# mega8_mega16.net
KiCad netlist of a schematic drawn in Altium Designer
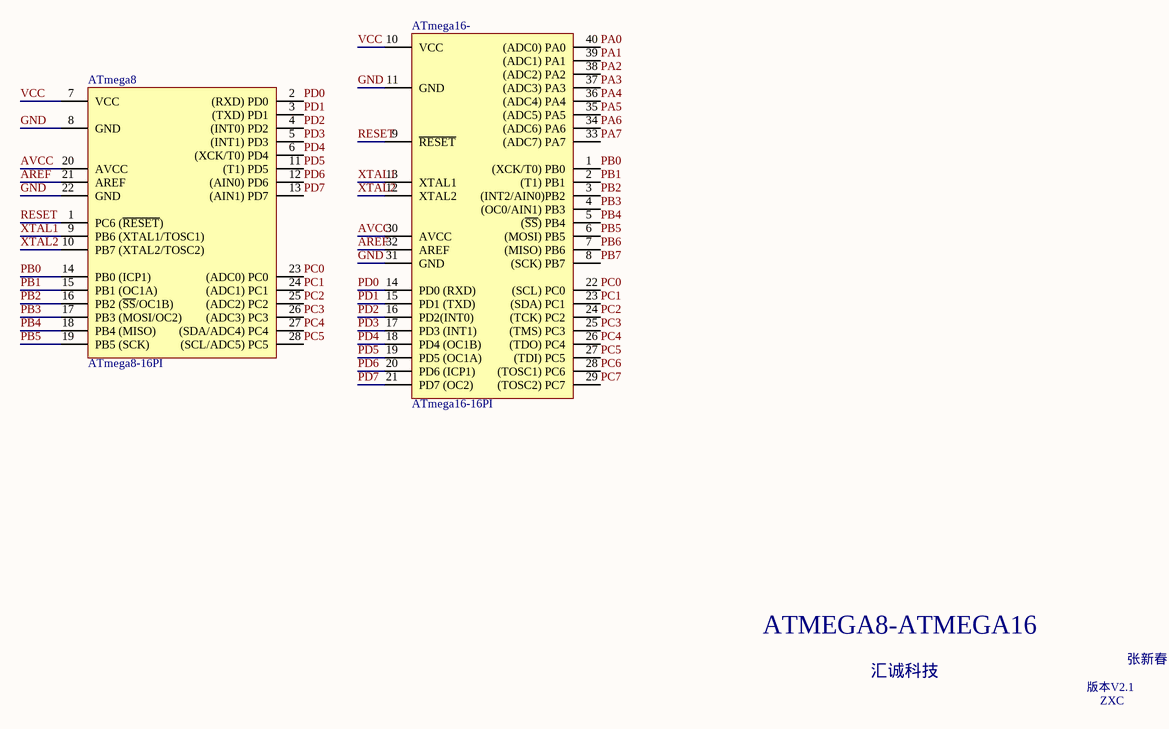
[diagram p0: mega8_mega16.SchDoc]

(export (version "E")
  (design (tool "Eeschema 10.0.6"))
  (components
    (comp (ref "ATmega8")
      (value "ATmega8-16PI")
      (footprint "底座DIP-28/引脚7.62mm")
      (description "8 位微处理器/28引脚")
      (fields (field (name "发布者") "磊元工作室"))
      (libsource (lib "微控制处理器") (part "ATmega8-P"))
    )
    (comp (ref "ATmega16-")
      (value "ATmega16-16PI")
      (footprint "底座DIP-40/引脚15.24mm")
      (description "8 位微处理器/40引脚")
      (fields (field (name "发布者") "磊元工作室"))
      (libsource (lib "微控制处理器") (part "ATmega16-P"))
    )
  )
  (nets
    (net (code "1") (name "/AREF") (class "Default")
      (node (ref "ATmega16-") (pin "32") (pinfunction "AREF_32") (pintype "passive"))
      (node (ref "ATmega8") (pin "21") (pinfunction "AREF_21") (pintype "passive"))
    )
    (net (code "2") (name "/AVCC") (class "Default")
      (node (ref "ATmega16-") (pin "30") (pinfunction "AVCC_30") (pintype "passive"))
      (node (ref "ATmega8") (pin "20") (pinfunction "AVCC_20") (pintype "passive"))
    )
    (net (code "3") (name "/GND") (class "Default")
      (node (ref "ATmega16-") (pin "11") (pinfunction "GND_11") (pintype "passive"))
      (node (ref "ATmega16-") (pin "31") (pinfunction "GND_31") (pintype "passive"))
      (node (ref "ATmega8") (pin "22") (pinfunction "GND_22") (pintype "passive"))
      (node (ref "ATmega8") (pin "8") (pinfunction "GND_8") (pintype "passive"))
    )
    (net (code "4") (name "/PA0") (class "Default")
      (node (ref "ATmega16-") (pin "40") (pinfunction "(ADC0)_PA0_40") (pintype "passive"))
    )
    (net (code "5") (name "/PA1") (class "Default")
      (node (ref "ATmega16-") (pin "39") (pinfunction "(ADC1)_PA1_39") (pintype "passive"))
    )
    (net (code "6") (name "/PA2") (class "Default")
      (node (ref "ATmega16-") (pin "38") (pinfunction "(ADC2)_PA2_38") (pintype "passive"))
    )
    (net (code "7") (name "/PA3") (class "Default")
      (node (ref "ATmega16-") (pin "37") (pinfunction "(ADC3)_PA3_37") (pintype "passive"))
    )
    (net (code "8") (name "/PA4") (class "Default")
      (node (ref "ATmega16-") (pin "36") (pinfunction "(ADC4)_PA4_36") (pintype "passive"))
    )
    (net (code "9") (name "/PA5") (class "Default")
      (node (ref "ATmega16-") (pin "35") (pinfunction "(ADC5)_PA5_35") (pintype "passive"))
    )
    (net (code "10") (name "/PA6") (class "Default")
      (node (ref "ATmega16-") (pin "34") (pinfunction "(ADC6)_PA6_34") (pintype "passive"))
    )
    (net (code "11") (name "/PA7") (class "Default")
      (node (ref "ATmega16-") (pin "33") (pinfunction "(ADC7)_PA7_33") (pintype "passive"))
    )
    (net (code "12") (name "/PB0") (class "Default")
      (node (ref "ATmega16-") (pin "1") (pinfunction "(XCK/T0)_PB0_1") (pintype "passive"))
      (node (ref "ATmega8") (pin "14") (pinfunction "PB0_(ICP1)_14") (pintype "passive"))
    )
    (net (code "13") (name "/PB1") (class "Default")
      (node (ref "ATmega16-") (pin "2") (pinfunction "(T1)_PB1_2") (pintype "passive"))
      (node (ref "ATmega8") (pin "15") (pinfunction "PB1_(OC1A)_15") (pintype "passive"))
    )
    (net (code "14") (name "/PB2") (class "Default")
      (node (ref "ATmega16-") (pin "3") (pinfunction "(INT2/AIN0)PB2_3") (pintype "passive"))
      (node (ref "ATmega8") (pin "16") (pinfunction "PB2_(~{SS}/OC1B)_16") (pintype "passive"))
    )
    (net (code "15") (name "/PB3") (class "Default")
      (node (ref "ATmega16-") (pin "4") (pinfunction "(OC0/AIN1)_PB3_4") (pintype "passive"))
      (node (ref "ATmega8") (pin "17") (pinfunction "PB3_(MOSI/OC2)_17") (pintype "passive"))
    )
    (net (code "16") (name "/PB4") (class "Default")
      (node (ref "ATmega16-") (pin "5") (pinfunction "(~{SS})_PB4_5") (pintype "passive"))
      (node (ref "ATmega8") (pin "18") (pinfunction "PB4_(MISO)_18") (pintype "passive"))
    )
    (net (code "17") (name "/PB5") (class "Default")
      (node (ref "ATmega16-") (pin "6") (pinfunction "(MOSI)_PB5_6") (pintype "passive"))
      (node (ref "ATmega8") (pin "19") (pinfunction "PB5_(SCK)_19") (pintype "passive"))
    )
    (net (code "18") (name "/PB6") (class "Default")
      (node (ref "ATmega16-") (pin "7") (pinfunction "(MISO)_PB6_7") (pintype "passive"))
    )
    (net (code "19") (name "/PB7") (class "Default")
      (node (ref "ATmega16-") (pin "8") (pinfunction "(SCK)_PB7_8") (pintype "passive"))
    )
    (net (code "20") (name "/PC0") (class "Default")
      (node (ref "ATmega16-") (pin "22") (pinfunction "(SCL)_PC0_22") (pintype "passive"))
      (node (ref "ATmega8") (pin "23") (pinfunction "(ADC0)_PC0_23") (pintype "passive"))
    )
    (net (code "21") (name "/PC1") (class "Default")
      (node (ref "ATmega16-") (pin "23") (pinfunction "(SDA)_PC1_23") (pintype "passive"))
      (node (ref "ATmega8") (pin "24") (pinfunction "(ADC1)_PC1_24") (pintype "passive"))
    )
    (net (code "22") (name "/PC2") (class "Default")
      (node (ref "ATmega16-") (pin "24") (pinfunction "(TCK)_PC2_24") (pintype "passive"))
      (node (ref "ATmega8") (pin "25") (pinfunction "(ADC2)_PC2_25") (pintype "passive"))
    )
    (net (code "23") (name "/PC3") (class "Default")
      (node (ref "ATmega16-") (pin "25") (pinfunction "(TMS)_PC3_25") (pintype "passive"))
      (node (ref "ATmega8") (pin "26") (pinfunction "(ADC3)_PC3_26") (pintype "passive"))
    )
    (net (code "24") (name "/PC4") (class "Default")
      (node (ref "ATmega16-") (pin "26") (pinfunction "(TDO)_PC4_26") (pintype "passive"))
      (node (ref "ATmega8") (pin "27") (pinfunction "(SDA/ADC4)_PC4_27") (pintype "passive"))
    )
    (net (code "25") (name "/PC5") (class "Default")
      (node (ref "ATmega16-") (pin "27") (pinfunction "(TDI)_PC5_27") (pintype "passive"))
      (node (ref "ATmega8") (pin "28") (pinfunction "(SCL/ADC5)_PC5_28") (pintype "passive"))
    )
    (net (code "26") (name "/PC6") (class "Default")
      (node (ref "ATmega16-") (pin "28") (pinfunction "(TOSC1)_PC6_28") (pintype "passive"))
    )
    (net (code "27") (name "/PC7") (class "Default")
      (node (ref "ATmega16-") (pin "29") (pinfunction "(TOSC2)_PC7_29") (pintype "passive"))
    )
    (net (code "28") (name "/PD0") (class "Default")
      (node (ref "ATmega16-") (pin "14") (pinfunction "PD0_(RXD)_14") (pintype "passive"))
      (node (ref "ATmega8") (pin "2") (pinfunction "(RXD)_PD0_2") (pintype "passive"))
    )
    (net (code "29") (name "/PD1") (class "Default")
      (node (ref "ATmega16-") (pin "15") (pinfunction "PD1_(TXD)_15") (pintype "passive"))
      (node (ref "ATmega8") (pin "3") (pinfunction "(TXD)_PD1_3") (pintype "passive"))
    )
    (net (code "30") (name "/PD2") (class "Default")
      (node (ref "ATmega16-") (pin "16") (pinfunction "PD2(INT0)_16") (pintype "passive"))
      (node (ref "ATmega8") (pin "4") (pinfunction "(INT0)_PD2_4") (pintype "passive"))
    )
    (net (code "31") (name "/PD3") (class "Default")
      (node (ref "ATmega16-") (pin "17") (pinfunction "PD3_(INT1)_17") (pintype "passive"))
      (node (ref "ATmega8") (pin "5") (pinfunction "(INT1)_PD3_5") (pintype "passive"))
    )
    (net (code "32") (name "/PD4") (class "Default")
      (node (ref "ATmega16-") (pin "18") (pinfunction "PD4_(OC1B)_18") (pintype "passive"))
      (node (ref "ATmega8") (pin "6") (pinfunction "(XCK/T0)_PD4_6") (pintype "passive"))
    )
    (net (code "33") (name "/PD5") (class "Default")
      (node (ref "ATmega16-") (pin "19") (pinfunction "PD5_(OC1A)_19") (pintype "passive"))
      (node (ref "ATmega8") (pin "11") (pinfunction "(T1)_PD5_11") (pintype "passive"))
    )
    (net (code "34") (name "/PD6") (class "Default")
      (node (ref "ATmega16-") (pin "20") (pinfunction "PD6_(ICP1)_20") (pintype "passive"))
      (node (ref "ATmega8") (pin "12") (pinfunction "(AIN0)_PD6_12") (pintype "passive"))
    )
    (net (code "35") (name "/PD7") (class "Default")
      (node (ref "ATmega16-") (pin "21") (pinfunction "PD7_(OC2)_21") (pintype "passive"))
      (node (ref "ATmega8") (pin "13") (pinfunction "(AIN1)_PD7_13") (pintype "passive"))
    )
    (net (code "36") (name "/RESET") (class "Default")
      (node (ref "ATmega16-") (pin "9") (pinfunction "~{RESET}_9") (pintype "passive"))
      (node (ref "ATmega8") (pin "1") (pinfunction "PC6_(~{RESET})_1") (pintype "passive"))
    )
    (net (code "37") (name "/VCC") (class "Default")
      (node (ref "ATmega16-") (pin "10") (pinfunction "VCC_10") (pintype "passive"))
      (node (ref "ATmega8") (pin "7") (pinfunction "VCC_7") (pintype "passive"))
    )
    (net (code "38") (name "/XTAL1") (class "Default")
      (node (ref "ATmega16-") (pin "13") (pinfunction "XTAL1_13") (pintype "passive"))
      (node (ref "ATmega8") (pin "9") (pinfunction "PB6_(XTAL1/TOSC1)_9") (pintype "passive"))
    )
    (net (code "39") (name "/XTAL2") (class "Default")
      (node (ref "ATmega16-") (pin "12") (pinfunction "XTAL2_12") (pintype "passive"))
      (node (ref "ATmega8") (pin "10") (pinfunction "PB7_(XTAL2/TOSC2)_10") (pintype "passive"))
    )
  )
)
